# buck_converter.net
KiCad netlist of a schematic drawn in Altium Designer
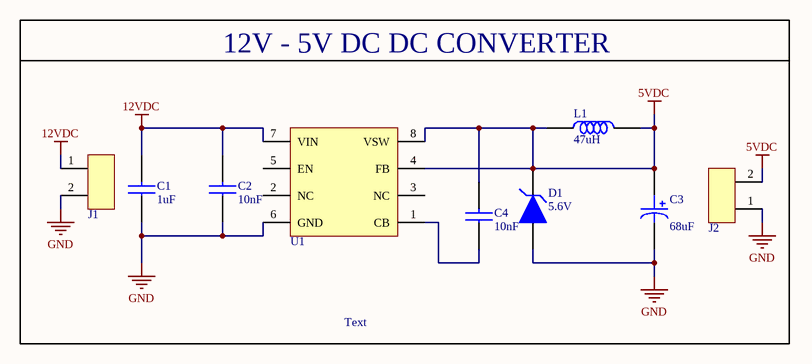
[diagram p0: buck_converter.SchDoc]

(export (version "E")
  (design (tool "Eeschema 10.0.6"))
  (components
    (comp (ref "C1")
      (value "CL21B105KBFNNNE")
      (footprint "CAP_0805")
      (description "CAP CER 1uF %10 0805")
      (fields
        (field (name "MANUFACTURER") "Samsung")
        (field (name "TOLERANCE") "10%")
        (field (name "CAPACITANCE") "1uF")
        (field (name "DESIGNED BY") "Yusuf DALAK")
      )
      (libsource (lib "UDEMY_Library") (part "CAP CER 1uF 0805"))
    )
    (comp (ref "C2")
      (value "0603B103K160CT")
      (footprint "CAP_0603")
      (description "CAP CER 10nF %10 0603")
      (fields
        (field (name "MANUFACTURER") "Walsin Technologies")
        (field (name "TOLERANCE") "10%")
        (field (name "CAPACITANCE") "10nF")
        (field (name "DESIGNED BY") "Yusuf DALAK")
      )
      (libsource (lib "UDEMY_Library") (part "CAP CER 10nF 0603"))
    )
    (comp (ref "C3")
      (value "EEV686M035A9HAA")
      (footprint "CAP_EEVseries")
      (description "Cap Aluminum Lytic 68uF 35V 20% (6.3 X 7.7mm) SMD 280mA 2000h 105C T/R")
      (fields
        (field (name "MANUFACTURER") "KEMET")
        (field (name "TOLERANCE") "20%")
        (field (name "CAPACITANCE") "68uF")
      )
      (libsource (lib "UDEMY_Library") (part "CAP ALU 68uF"))
    )
    (comp (ref "C4")
      (value "0603B103K160CT")
      (footprint "CAP_0603")
      (description "CAP CER 10nF %10 0603")
      (fields
        (field (name "MANUFACTURER") "Walsin Technologies")
        (field (name "TOLERANCE") "10%")
        (field (name "CAPACITANCE") "10nF")
        (field (name "DESIGNED BY") "Yusuf DALAK")
      )
      (libsource (lib "UDEMY_Library") (part "CAP CER 10nF 0603"))
    )
    (comp (ref "D1")
      (value "1SMB5919BT3G")
      (footprint "SMB")
      (description "Diode Zener Single 5.6V 5% 3W 2-Pin SMB T/R")
      (fields
        (field (name "MANUFACTURER") "ON Semiconductor")
        (field (name "TOLERANCE") "5%")
        (field (name "WORKING VOLTAGE") "5.6V")
        (field (name "DESIGNED BY") "Yusuf DALAK")
      )
      (libsource (lib "UDEMY_Library") (part "1SMB5919BT3G"))
    )
    (comp (ref "J1")
      (value "TBP01R1-508-02BE")
      (footprint "TBP01R1-508")
      (description "Conn Shrouded Header HDR 2 POS 5.08mm Solder RA Side Entry Thru-Hole Bag")
      (fields (field (name "MANUFACTURER") "CUI") (field (name "DESIGNED BY") "Yusuf DALAK"))
      (libsource (lib "UDEMY_Library") (part "TBP01R1-508-02BE"))
    )
    (comp (ref "J2")
      (value "TBP01R1-508-02BE")
      (footprint "TBP01R1-508")
      (description "Conn Shrouded Header HDR 2 POS 5.08mm Solder RA Side Entry Thru-Hole Bag")
      (fields (field (name "MANUFACTURER") "CUI") (field (name "DESIGNED BY") "Yusuf DALAK"))
      (libsource (lib "") (part "TBP01R1-508-02BE_1"))
    )
    (comp (ref "L1")
      (value "78438335470")
      (footprint "IND_1212")
      (description "FIXED IND 47UH 390MA 2.3 OHM SMD")
      (fields
        (field (name "MANUFACTURER") "Wurth Electronics")
        (field (name "TOLERANCE") "30%")
        (field (name "INDUCTANCE") "47uH")
        (field (name "DESIGNED BY") "Yusuf DALAK")
      )
      (libsource (lib "UDEMY_Library") (part "IND 47uH"))
    )
    (comp (ref "U1")
      (value "LM2675MX-12/NOPB")
      (footprint "SOIC8")
      (description "Switching Voltage Regulators Pwr Cnvtr Hi Eff 1A SD Vtg Reg")
      (fields
        (field (name "MANUFACTURER") "TI National Semiconductor")
        (field (name "DESIGNED BY") "Yusuf DALAK")
      )
      (libsource (lib "UDEMY_Library") (part "LM2675MX-12/NOPB"))
    )
  )
  (nets
    (net (code "1") (name "5VDC") (class "Default")
      (node (ref "C3") (pin "1") (pinfunction "1_1") (pintype "passive"))
      (node (ref "C4") (pin "2") (pinfunction "2_2") (pintype "passive"))
      (node (ref "D1") (pin "C") (pinfunction "C_C") (pintype "passive"))
      (node (ref "J2") (pin "2") (pinfunction "2_2") (pintype "power_in"))
      (node (ref "L1") (pin "1") (pinfunction "1_1") (pintype "passive"))
      (node (ref "L1") (pin "2") (pinfunction "2_2") (pintype "passive"))
      (node (ref "U1") (pin "4") (pinfunction "FB_4") (pintype "passive"))
      (node (ref "U1") (pin "8") (pinfunction "VSW_8") (pintype "passive"))
    )
    (net (code "2") (name "12VDC") (class "Default")
      (node (ref "C1") (pin "2") (pinfunction "2_2") (pintype "passive"))
      (node (ref "C2") (pin "2") (pinfunction "2_2") (pintype "passive"))
      (node (ref "J1") (pin "1") (pinfunction "1_1") (pintype "power_in"))
      (node (ref "U1") (pin "7") (pinfunction "VIN_7") (pintype "passive"))
    )
    (net (code "3") (name "GND") (class "Default")
      (node (ref "C1") (pin "1") (pinfunction "1_1") (pintype "passive"))
      (node (ref "C2") (pin "1") (pinfunction "1_1") (pintype "passive"))
      (node (ref "C3") (pin "2") (pinfunction "2_2") (pintype "passive"))
      (node (ref "D1") (pin "A") (pinfunction "A_A") (pintype "passive"))
      (node (ref "J1") (pin "2") (pinfunction "2_2") (pintype "power_in"))
      (node (ref "J2") (pin "1") (pinfunction "1_1") (pintype "power_in"))
      (node (ref "U1") (pin "6") (pinfunction "GND_6") (pintype "passive"))
    )
    (net (code "4") (name "Net-(U1-CB)") (class "Default")
      (node (ref "C4") (pin "1") (pinfunction "1_1") (pintype "passive"))
      (node (ref "U1") (pin "1") (pinfunction "CB_1") (pintype "passive"))
    )
    (net (code "5") (name "unconnected-(U1-EN-Pad5)") (class "Default")
      (node (ref "U1") (pin "5") (pinfunction "EN_5") (pintype "passive"))
    )
    (net (code "6") (name "unconnected-(U1-NC-Pad2)") (class "Default")
      (node (ref "U1") (pin "2") (pinfunction "NC_2") (pintype "passive"))
    )
    (net (code "7") (name "unconnected-(U1-NC-Pad3)") (class "Default")
      (node (ref "U1") (pin "3") (pinfunction "NC_3") (pintype "passive"))
    )
  )
)
